# chipchestra-v05-analog-inputs.net
KiCad netlist of a schematic drawn in EAGLE
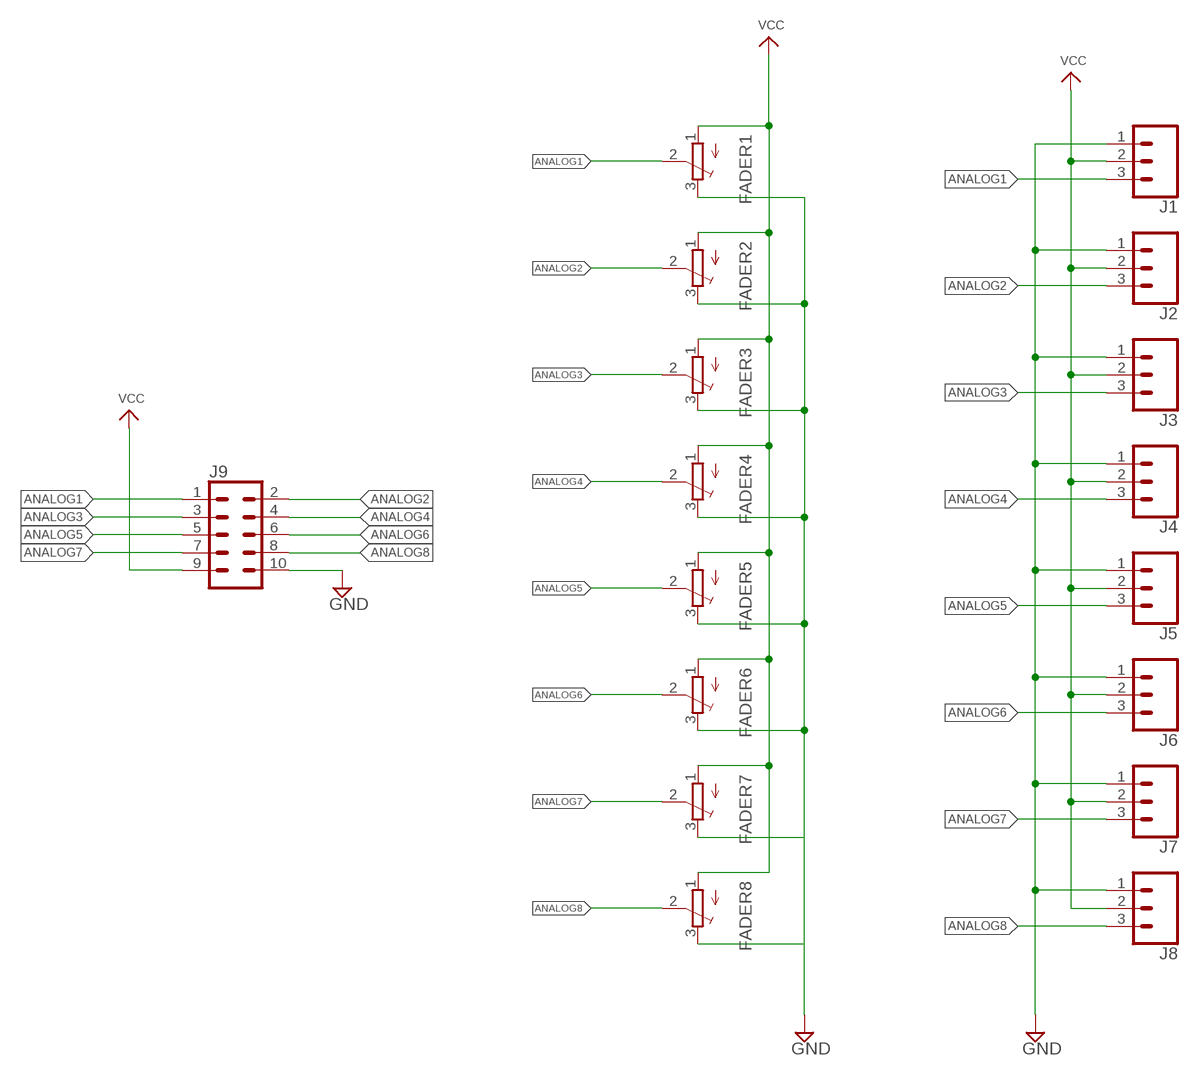
[diagram p0: schematic, sheet 1]

(export (version "E")
  (design (tool "Eeschema 10.0.6"))
  (components
    (comp (ref "FADER1")
      (value "TRIMPOT3386")
      (footprint "eagle-import:TRIM-3386")
      (libsource (lib "eagle-import") (part "TRIMPOT3386"))
    )
    (comp (ref "FADER2")
      (value "TRIMPOT3386")
      (footprint "eagle-import:TRIM-3386")
      (libsource (lib "eagle-import") (part "TRIMPOT3386"))
    )
    (comp (ref "FADER3")
      (value "TRIMPOT3386")
      (footprint "eagle-import:TRIM-3386")
      (libsource (lib "eagle-import") (part "TRIMPOT3386"))
    )
    (comp (ref "FADER4")
      (value "TRIMPOT3386")
      (footprint "eagle-import:TRIM-3386")
      (libsource (lib "eagle-import") (part "TRIMPOT3386"))
    )
    (comp (ref "FADER5")
      (value "TRIMPOT3386")
      (footprint "eagle-import:TRIM-3386")
      (libsource (lib "eagle-import") (part "TRIMPOT3386"))
    )
    (comp (ref "FADER6")
      (value "TRIMPOT3386")
      (footprint "eagle-import:TRIM-3386")
      (libsource (lib "eagle-import") (part "TRIMPOT3386"))
    )
    (comp (ref "FADER7")
      (value "TRIMPOT3386")
      (footprint "eagle-import:TRIM-3386")
      (libsource (lib "eagle-import") (part "TRIMPOT3386"))
    )
    (comp (ref "FADER8")
      (value "TRIMPOT3386")
      (footprint "eagle-import:TRIM-3386")
      (libsource (lib "eagle-import") (part "TRIMPOT3386"))
    )
    (comp (ref "J1")
      (value "CONN_03LOCK")
      (footprint "eagle-import:1X03_LOCK")
      (libsource (lib "eagle-import") (part "CONN_03LOCK"))
    )
    (comp (ref "J2")
      (value "CONN_03LOCK")
      (footprint "eagle-import:1X03_LOCK")
      (libsource (lib "eagle-import") (part "CONN_03LOCK"))
    )
    (comp (ref "J3")
      (value "CONN_03LOCK")
      (footprint "eagle-import:1X03_LOCK")
      (libsource (lib "eagle-import") (part "CONN_03LOCK"))
    )
    (comp (ref "J4")
      (value "CONN_03LOCK")
      (footprint "eagle-import:1X03_LOCK")
      (libsource (lib "eagle-import") (part "CONN_03LOCK"))
    )
    (comp (ref "J5")
      (value "CONN_03LOCK")
      (footprint "eagle-import:1X03_LOCK")
      (libsource (lib "eagle-import") (part "CONN_03LOCK"))
    )
    (comp (ref "J6")
      (value "CONN_03LOCK")
      (footprint "eagle-import:1X03_LOCK")
      (libsource (lib "eagle-import") (part "CONN_03LOCK"))
    )
    (comp (ref "J7")
      (value "CONN_03LOCK")
      (footprint "eagle-import:1X03_LOCK")
      (libsource (lib "eagle-import") (part "CONN_03LOCK"))
    )
    (comp (ref "J8")
      (value "CONN_03LOCK")
      (footprint "eagle-import:1X03_LOCK")
      (libsource (lib "eagle-import") (part "CONN_03LOCK"))
    )
    (comp (ref "J9")
      (value "CONN_05X2SHD_LOCK")
      (footprint "eagle-import:2X5-SHROUDED_LOCK")
      (libsource (lib "eagle-import") (part "CONN_05X2SHD_LOCK"))
    )
  )
  (nets
    (net (code "1") (name "ANALOG1") (class "Default")
      (node (ref "FADER1") (pin "2") (pinfunction "S_2") (pintype "passive"))
      (node (ref "J1") (pin "3") (pinfunction "3_3") (pintype "passive"))
      (node (ref "J9") (pin "1") (pinfunction "1_1") (pintype "passive"))
    )
    (net (code "2") (name "ANALOG2") (class "Default")
      (node (ref "FADER2") (pin "2") (pinfunction "S_2") (pintype "passive"))
      (node (ref "J2") (pin "3") (pinfunction "3_3") (pintype "passive"))
      (node (ref "J9") (pin "2") (pinfunction "2_2") (pintype "passive"))
    )
    (net (code "3") (name "ANALOG3") (class "Default")
      (node (ref "FADER3") (pin "2") (pinfunction "S_2") (pintype "passive"))
      (node (ref "J3") (pin "3") (pinfunction "3_3") (pintype "passive"))
      (node (ref "J9") (pin "3") (pinfunction "3_3") (pintype "passive"))
    )
    (net (code "4") (name "ANALOG4") (class "Default")
      (node (ref "FADER4") (pin "2") (pinfunction "S_2") (pintype "passive"))
      (node (ref "J4") (pin "3") (pinfunction "3_3") (pintype "passive"))
      (node (ref "J9") (pin "4") (pinfunction "4_4") (pintype "passive"))
    )
    (net (code "5") (name "ANALOG5") (class "Default")
      (node (ref "FADER5") (pin "2") (pinfunction "S_2") (pintype "passive"))
      (node (ref "J5") (pin "3") (pinfunction "3_3") (pintype "passive"))
      (node (ref "J9") (pin "5") (pinfunction "5_5") (pintype "passive"))
    )
    (net (code "6") (name "ANALOG6") (class "Default")
      (node (ref "FADER6") (pin "2") (pinfunction "S_2") (pintype "passive"))
      (node (ref "J6") (pin "3") (pinfunction "3_3") (pintype "passive"))
      (node (ref "J9") (pin "6") (pinfunction "6_6") (pintype "passive"))
    )
    (net (code "7") (name "ANALOG7") (class "Default")
      (node (ref "FADER7") (pin "2") (pinfunction "S_2") (pintype "passive"))
      (node (ref "J7") (pin "3") (pinfunction "3_3") (pintype "passive"))
      (node (ref "J9") (pin "7") (pinfunction "7_7") (pintype "passive"))
    )
    (net (code "8") (name "ANALOG8") (class "Default")
      (node (ref "FADER8") (pin "2") (pinfunction "S_2") (pintype "passive"))
      (node (ref "J8") (pin "3") (pinfunction "3_3") (pintype "passive"))
      (node (ref "J9") (pin "8") (pinfunction "8_8") (pintype "passive"))
    )
    (net (code "9") (name "GND") (class "Default")
      (node (ref "FADER1") (pin "3") (pinfunction "E_3") (pintype "passive"))
      (node (ref "FADER2") (pin "3") (pinfunction "E_3") (pintype "passive"))
      (node (ref "FADER3") (pin "3") (pinfunction "E_3") (pintype "passive"))
      (node (ref "FADER4") (pin "3") (pinfunction "E_3") (pintype "passive"))
      (node (ref "FADER5") (pin "3") (pinfunction "E_3") (pintype "passive"))
      (node (ref "FADER6") (pin "3") (pinfunction "E_3") (pintype "passive"))
      (node (ref "FADER7") (pin "3") (pinfunction "E_3") (pintype "passive"))
      (node (ref "FADER8") (pin "3") (pinfunction "E_3") (pintype "passive"))
      (node (ref "J1") (pin "1") (pinfunction "1_1") (pintype "passive"))
      (node (ref "J2") (pin "1") (pinfunction "1_1") (pintype "passive"))
      (node (ref "J3") (pin "1") (pinfunction "1_1") (pintype "passive"))
      (node (ref "J4") (pin "1") (pinfunction "1_1") (pintype "passive"))
      (node (ref "J5") (pin "1") (pinfunction "1_1") (pintype "passive"))
      (node (ref "J6") (pin "1") (pinfunction "1_1") (pintype "passive"))
      (node (ref "J7") (pin "1") (pinfunction "1_1") (pintype "passive"))
      (node (ref "J8") (pin "1") (pinfunction "1_1") (pintype "passive"))
      (node (ref "J9") (pin "10") (pinfunction "10_10") (pintype "passive"))
    )
    (net (code "10") (name "VCC") (class "Default")
      (node (ref "FADER1") (pin "1") (pinfunction "A_1") (pintype "passive"))
      (node (ref "FADER2") (pin "1") (pinfunction "A_1") (pintype "passive"))
      (node (ref "FADER3") (pin "1") (pinfunction "A_1") (pintype "passive"))
      (node (ref "FADER4") (pin "1") (pinfunction "A_1") (pintype "passive"))
      (node (ref "FADER5") (pin "1") (pinfunction "A_1") (pintype "passive"))
      (node (ref "FADER6") (pin "1") (pinfunction "A_1") (pintype "passive"))
      (node (ref "FADER7") (pin "1") (pinfunction "A_1") (pintype "passive"))
      (node (ref "FADER8") (pin "1") (pinfunction "A_1") (pintype "passive"))
      (node (ref "J1") (pin "2") (pinfunction "2_2") (pintype "passive"))
      (node (ref "J2") (pin "2") (pinfunction "2_2") (pintype "passive"))
      (node (ref "J3") (pin "2") (pinfunction "2_2") (pintype "passive"))
      (node (ref "J4") (pin "2") (pinfunction "2_2") (pintype "passive"))
      (node (ref "J5") (pin "2") (pinfunction "2_2") (pintype "passive"))
      (node (ref "J6") (pin "2") (pinfunction "2_2") (pintype "passive"))
      (node (ref "J7") (pin "2") (pinfunction "2_2") (pintype "passive"))
      (node (ref "J8") (pin "2") (pinfunction "2_2") (pintype "passive"))
      (node (ref "J9") (pin "9") (pinfunction "9_9") (pintype "passive"))
    )
  )
)
